# supercap.net
KiCad netlist of a schematic drawn in Altium Designer
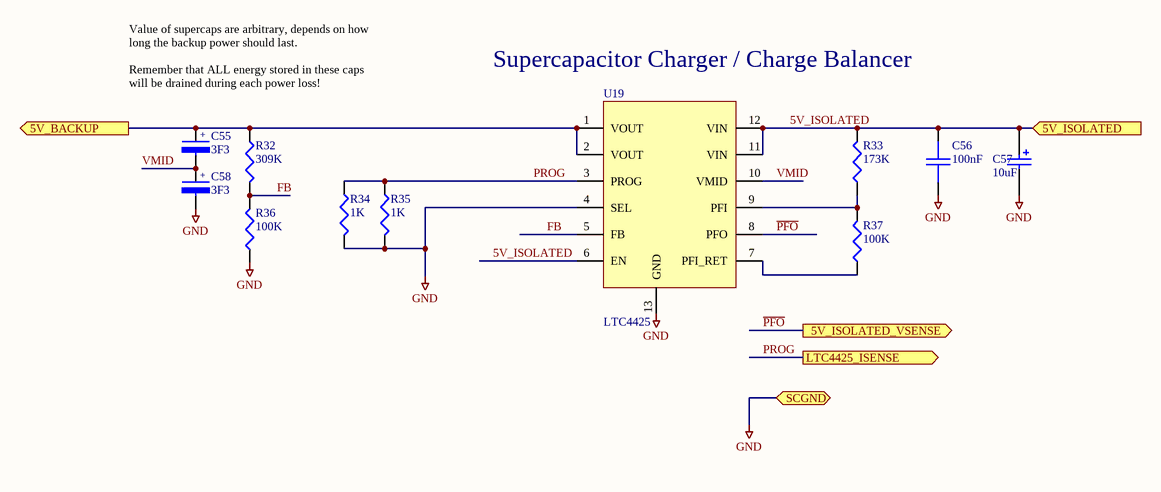
[diagram p0: supercap.SchDoc]

(export (version "E")
  (design (tool "Eeschema 10.0.6"))
  (components
    (comp (ref "C55")
      (value "3F3")
      (footprint "ELECTROLYTIC-5-32")
      (description "Supercap")
      (libsource (lib "RCLDQ") (part "CAP-POL"))
    )
    (comp (ref "C56")
      (value "100nF")
      (footprint "0603")
      (description "Capacitor")
      (libsource (lib "RCLDQ") (part "CAP"))
    )
    (comp (ref "C57")
      (value "10uF")
      (footprint "MCCT-CASEA")
      (description "Polarized Capacitor (Surface Mount)")
      (libsource (lib "RCLDQ") (part "CAP POL3"))
    )
    (comp (ref "C58")
      (value "3F3")
      (footprint "ELECTROLYTIC-5-32")
      (description "Supercap")
      (libsource (lib "RCLDQ") (part "CAP-POL"))
    )
    (comp (ref "R32")
      (value "309K")
      (footprint "0603")
      (description "Resistor")
      (libsource (lib "RCLDQ") (part "RES1"))
    )
    (comp (ref "R33")
      (value "173K")
      (footprint "0603")
      (description "Resistor")
      (libsource (lib "RCLDQ") (part "RES1"))
    )
    (comp (ref "R34")
      (value "1K")
      (footprint "0603")
      (description "Resistor")
      (libsource (lib "RCLDQ") (part "RES1"))
    )
    (comp (ref "R35")
      (value "1K")
      (footprint "0603")
      (description "Resistor")
      (libsource (lib "RCLDQ") (part "RES1"))
    )
    (comp (ref "R36")
      (value "100K")
      (footprint "0603")
      (description "Resistor")
      (libsource (lib "RCLDQ") (part "RES1"))
    )
    (comp (ref "R37")
      (value "100K")
      (footprint "0603")
      (description "Resistor")
      (libsource (lib "RCLDQ") (part "RES1"))
    )
    (comp (ref "U19")
      (value "LTC4425")
      (footprint "MS-12")
      (description "Supercapacitor Charger")
      (libsource (lib "sion") (part "LTC4425"))
    )
  )
  (nets
    (net (code "1") (name "/5V_BACKUP") (class "Default")
      (node (ref "C55") (pin "1") (pinfunction "1_1") (pintype "passive"))
      (node (ref "R32") (pin "1") (pinfunction "1_1") (pintype "passive"))
      (node (ref "U19") (pin "1") (pinfunction "VOUT_1") (pintype "passive"))
      (node (ref "U19") (pin "2") (pinfunction "VOUT_2") (pintype "passive"))
    )
    (net (code "2") (name "/5V_ISOLATED") (class "Default")
      (node (ref "C56") (pin "1") (pinfunction "1_1") (pintype "passive"))
      (node (ref "C57") (pin "1") (pinfunction "1_1") (pintype "passive"))
      (node (ref "R33") (pin "2") (pinfunction "2_2") (pintype "passive"))
      (node (ref "U19") (pin "11") (pinfunction "VIN_11") (pintype "passive"))
      (node (ref "U19") (pin "12") (pinfunction "VIN_12") (pintype "passive"))
      (node (ref "U19") (pin "6") (pinfunction "EN_6") (pintype "passive"))
    )
    (net (code "3") (name "/FB") (class "Default")
      (node (ref "R32") (pin "2") (pinfunction "2_2") (pintype "passive"))
      (node (ref "R36") (pin "2") (pinfunction "2_2") (pintype "passive"))
      (node (ref "U19") (pin "5") (pinfunction "FB_5") (pintype "passive"))
    )
    (net (code "4") (name "/PROG") (class "Default")
      (node (ref "R34") (pin "1") (pinfunction "1_1") (pintype "passive"))
      (node (ref "R35") (pin "1") (pinfunction "1_1") (pintype "passive"))
      (node (ref "U19") (pin "3") (pinfunction "PROG_3") (pintype "passive"))
    )
    (net (code "5") (name "/VMID") (class "Default")
      (node (ref "C55") (pin "2") (pinfunction "2_2") (pintype "passive"))
      (node (ref "C58") (pin "1") (pinfunction "1_1") (pintype "passive"))
      (node (ref "U19") (pin "10") (pinfunction "VMID_10") (pintype "passive"))
    )
    (net (code "6") (name "/~{PFO}") (class "Default")
      (node (ref "U19") (pin "8") (pinfunction "PFO_8") (pintype "passive"))
    )
    (net (code "7") (name "GND") (class "Default")
      (node (ref "C56") (pin "2") (pinfunction "2_2") (pintype "passive"))
      (node (ref "C57") (pin "2") (pinfunction "2_2") (pintype "passive"))
      (node (ref "C58") (pin "2") (pinfunction "2_2") (pintype "passive"))
      (node (ref "R34") (pin "2") (pinfunction "2_2") (pintype "passive"))
      (node (ref "R35") (pin "2") (pinfunction "2_2") (pintype "passive"))
      (node (ref "R36") (pin "1") (pinfunction "1_1") (pintype "passive"))
      (node (ref "U19") (pin "13") (pinfunction "GND_13") (pintype "passive"))
      (node (ref "U19") (pin "4") (pinfunction "SEL_4") (pintype "passive"))
    )
    (net (code "8") (name "Net-(U19-PFI)") (class "Default")
      (node (ref "R33") (pin "1") (pinfunction "1_1") (pintype "passive"))
      (node (ref "R37") (pin "2") (pinfunction "2_2") (pintype "passive"))
      (node (ref "U19") (pin "9") (pinfunction "PFI_9") (pintype "passive"))
    )
    (net (code "9") (name "Net-(U19-PFI_RET)") (class "Default")
      (node (ref "R37") (pin "1") (pinfunction "1_1") (pintype "passive"))
      (node (ref "U19") (pin "7") (pinfunction "PFI_RET_7") (pintype "passive"))
    )
  )
)
